# CAN.net
KiCad netlist of a schematic drawn in Altium Designer
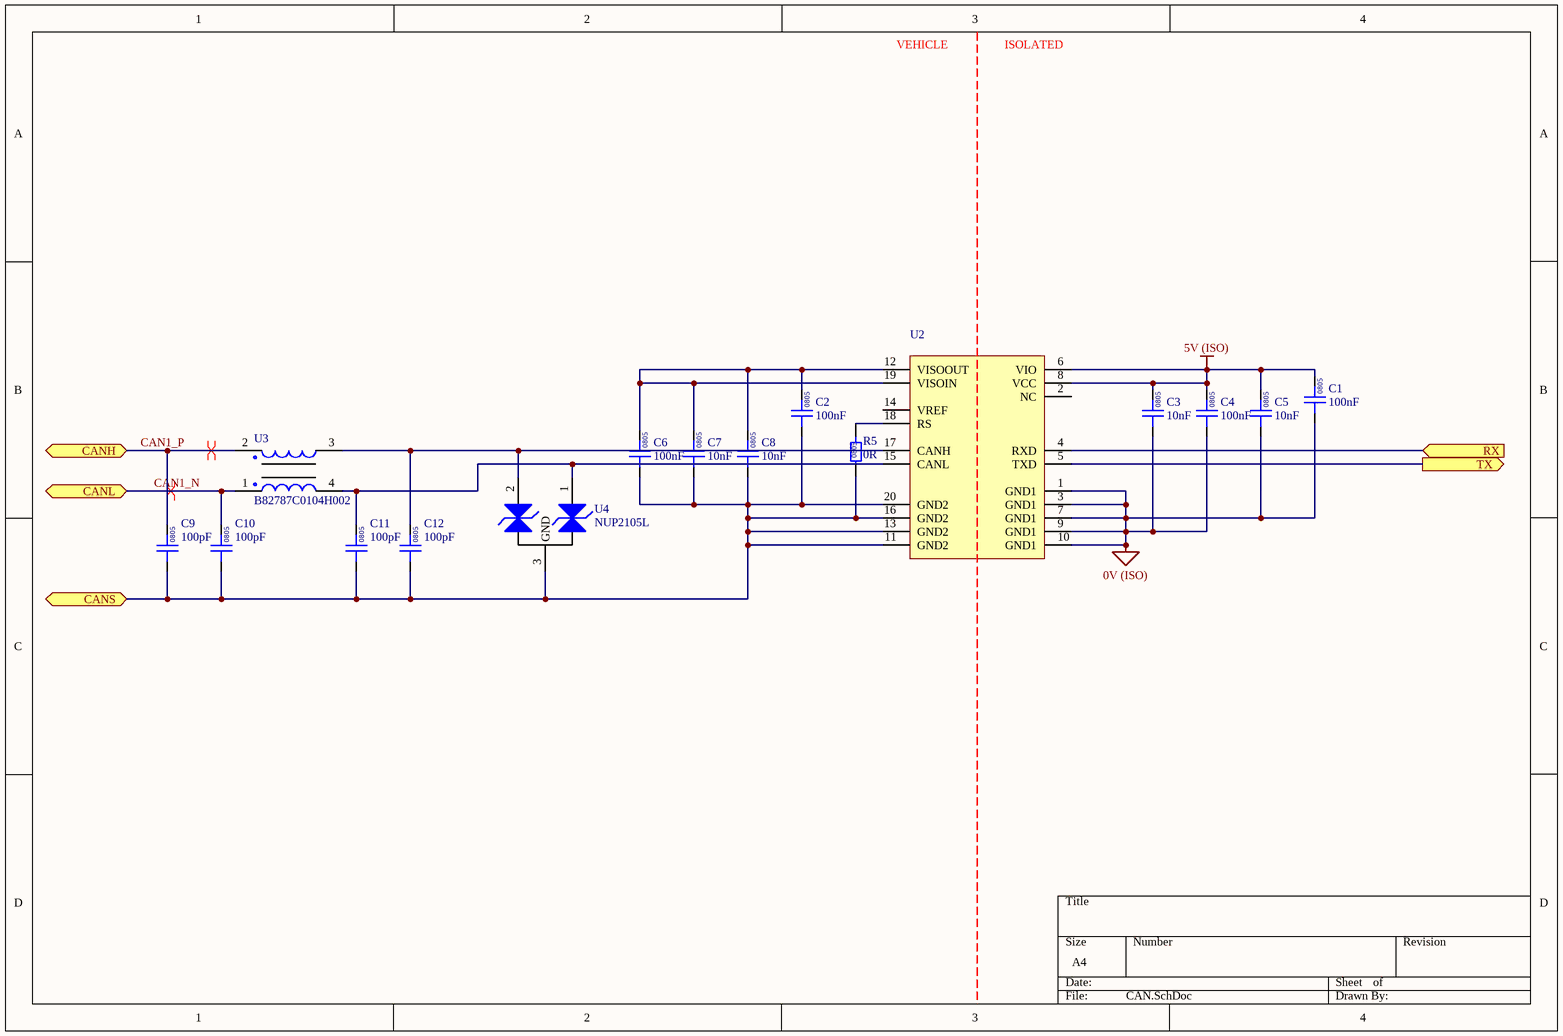
[diagram p0: CAN.SchDoc]

(export (version "E")
  (design (tool "Eeschema 10.0.6"))
  (components
    (comp (ref "C1")
      (value "100nF")
      (footprint "0805")
      (fields
        (field (name "PART NUMBER") "GCM21BR71H104KA37L")
        (field (name "TOLERANCE") "±10%")
        (field (name "MANUFACTURER") "muRata")
      )
      (libsource (lib "ts_standard_library") (part "Capacitor 0805"))
    )
    (comp (ref "C2")
      (value "100nF")
      (footprint "0805")
      (fields
        (field (name "PART NUMBER") "GCM21BR71H104KA37L")
        (field (name "TOLERANCE") "±10%")
        (field (name "MANUFACTURER") "muRata")
      )
      (libsource (lib "ts_standard_library") (part "Capacitor 0805"))
    )
    (comp (ref "C3")
      (value "10nF")
      (footprint "0805")
      (fields
        (field (name "PART NUMBER") "GCM2195C1H103JA16D")
        (field (name "TOLERANCE") "±5%")
        (field (name "MANUFACTURER") "muRata")
      )
      (libsource (lib "ts_standard_library") (part "Capacitor 0805"))
    )
    (comp (ref "C4")
      (value "100nF")
      (footprint "0805")
      (fields
        (field (name "PART NUMBER") "GCM21BR71H104KA37L")
        (field (name "TOLERANCE") "±10%")
        (field (name "MANUFACTURER") "muRata")
      )
      (libsource (lib "ts_standard_library") (part "Capacitor 0805"))
    )
    (comp (ref "C5")
      (value "10nF")
      (footprint "0805")
      (fields
        (field (name "PART NUMBER") "GCM2195C1H103JA16D")
        (field (name "TOLERANCE") "±5%")
        (field (name "MANUFACTURER") "muRata")
      )
      (libsource (lib "ts_standard_library") (part "Capacitor 0805"))
    )
    (comp (ref "C6")
      (value "100nF")
      (footprint "0805")
      (fields
        (field (name "PART NUMBER") "GCM21BR71H104KA37L")
        (field (name "TOLERANCE") "±10%")
        (field (name "MANUFACTURER") "muRata")
      )
      (libsource (lib "ts_standard_library") (part "Capacitor 0805"))
    )
    (comp (ref "C7")
      (value "10nF")
      (footprint "0805")
      (fields
        (field (name "PART NUMBER") "GCM2195C1H103JA16D")
        (field (name "TOLERANCE") "±5%")
        (field (name "MANUFACTURER") "muRata")
      )
      (libsource (lib "ts_standard_library") (part "Capacitor 0805"))
    )
    (comp (ref "C8")
      (value "10nF")
      (footprint "0805")
      (fields
        (field (name "PART NUMBER") "GCM2195C1H103JA16D")
        (field (name "TOLERANCE") "±5%")
        (field (name "MANUFACTURER") "muRata")
      )
      (libsource (lib "ts_standard_library") (part "Capacitor 0805"))
    )
    (comp (ref "C9")
      (value "100pF")
      (footprint "0805")
      (fields
        (field (name "PART NUMBER") "GCM2165C1H101JA16D")
        (field (name "TOLERANCE") "±5%")
        (field (name "MANUFACTURER") "muRata")
      )
      (libsource (lib "ts_standard_library") (part "Capacitor 0805"))
    )
    (comp (ref "C10")
      (value "100pF")
      (footprint "0805")
      (fields
        (field (name "PART NUMBER") "GCM2165C1H101JA16D")
        (field (name "TOLERANCE") "±5%")
        (field (name "MANUFACTURER") "muRata")
      )
      (libsource (lib "ts_standard_library") (part "Capacitor 0805"))
    )
    (comp (ref "C11")
      (value "100pF")
      (footprint "0805")
      (fields
        (field (name "PART NUMBER") "GCM2165C1H101JA16D")
        (field (name "TOLERANCE") "±5%")
        (field (name "MANUFACTURER") "muRata")
      )
      (libsource (lib "ts_standard_library") (part "Capacitor 0805"))
    )
    (comp (ref "C12")
      (value "100pF")
      (footprint "0805")
      (fields
        (field (name "PART NUMBER") "GCM2165C1H101JA16D")
        (field (name "TOLERANCE") "±5%")
        (field (name "MANUFACTURER") "muRata")
      )
      (libsource (lib "ts_standard_library") (part "Capacitor 0805"))
    )
    (comp (ref "R5")
      (value "0R")
      (footprint "0805")
      (fields
        (field (name "PART NUMBER") "RC0805FR070RL")
        (field (name "MANUFACTURER") "YAGEO")
        (field (name "TOLERANCE") "0.01")
      )
      (libsource (lib "ts_standard_library") (part "Resistor 0805"))
    )
    (comp (ref "U2")
      (value "~")
      (footprint "AD SOIC-W 20")
      (description "Isolated CAN Transceiver")
      (fields (field (name "PART NUMBER") "ADM3053") (field (name "MANUFACTURER") "Analogue Devices"))
      (libsource (lib "ts_standard_library") (part "ADM3053"))
    )
    (comp (ref "U3")
      (value "B82787C0104H002")
      (footprint "TDK 4-PC Pad")
      (fields
        (field (name "MANUFACTURER") "EPCOS (TDK)")
        (field (name "DIGIKEY PART NUMBER") "495-4598-1-ND")
      )
      (libsource (lib "ts_standard_library") (part "B82787C0104H002"))
    )
    (comp (ref "U4")
      (value "NUP2105L")
      (footprint "ON SOT-23")
      (description "Dual Line CAN Bus Protector")
      (fields
        (field (name "MANUFACTURER") "ON Semiconductor")
        (field (name "DIGIKEY PART NUMBER") "NUP2105LT1GOSCT-ND")
      )
      (libsource (lib "ts_standard_library") (part "NUP2105L"))
    )
  )
  (nets
    (net (code "1") (name "/CAN1_N") (class "Default")
      (node (ref "C10") (pin "2") (pinfunction "2_2") (pintype "passive"))
      (node (ref "U3") (pin "1") (pinfunction "1_1") (pintype "passive"))
    )
    (net (code "2") (name "/CAN1_P") (class "Default")
      (node (ref "C9") (pin "2") (pinfunction "2_2") (pintype "passive"))
      (node (ref "U3") (pin "2") (pinfunction "2_2") (pintype "passive"))
    )
    (net (code "3") (name "/CANS") (class "Default")
      (node (ref "C10") (pin "1") (pinfunction "1_1") (pintype "passive"))
      (node (ref "C11") (pin "1") (pinfunction "1_1") (pintype "passive"))
      (node (ref "C12") (pin "1") (pinfunction "1_1") (pintype "passive"))
      (node (ref "C2") (pin "1") (pinfunction "1_1") (pintype "passive"))
      (node (ref "C6") (pin "1") (pinfunction "1_1") (pintype "passive"))
      (node (ref "C7") (pin "1") (pinfunction "1_1") (pintype "passive"))
      (node (ref "C8") (pin "1") (pinfunction "1_1") (pintype "passive"))
      (node (ref "C9") (pin "1") (pinfunction "1_1") (pintype "passive"))
      (node (ref "R5") (pin "1") (pinfunction "1_1") (pintype "passive"))
      (node (ref "U2") (pin "11") (pinfunction "GND2_11") (pintype "passive"))
      (node (ref "U2") (pin "13") (pinfunction "GND2_13") (pintype "passive"))
      (node (ref "U2") (pin "16") (pinfunction "GND2_16") (pintype "passive"))
      (node (ref "U2") (pin "20") (pinfunction "GND2_20") (pintype "passive"))
      (node (ref "U4") (pin "3") (pinfunction "GND_3") (pintype "passive"))
    )
    (net (code "4") (name "/RX") (class "Default")
      (node (ref "U2") (pin "4") (pinfunction "RXD_4") (pintype "passive"))
    )
    (net (code "5") (name "/TX") (class "Default")
      (node (ref "U2") (pin "5") (pinfunction "TXD_5") (pintype "passive"))
    )
    (net (code "6") (name "0V (ISO)") (class "Default")
      (node (ref "C1") (pin "1") (pinfunction "1_1") (pintype "passive"))
      (node (ref "C3") (pin "1") (pinfunction "1_1") (pintype "passive"))
      (node (ref "C4") (pin "1") (pinfunction "1_1") (pintype "passive"))
      (node (ref "C5") (pin "1") (pinfunction "1_1") (pintype "passive"))
      (node (ref "U2") (pin "1") (pinfunction "GND1_1") (pintype "passive"))
      (node (ref "U2") (pin "10") (pinfunction "GND1_10") (pintype "passive"))
      (node (ref "U2") (pin "3") (pinfunction "GND1_3") (pintype "passive"))
      (node (ref "U2") (pin "7") (pinfunction "GND1_7") (pintype "passive"))
      (node (ref "U2") (pin "9") (pinfunction "GND1_9") (pintype "passive"))
    )
    (net (code "7") (name "5V (ISO)") (class "Default")
      (node (ref "C1") (pin "2") (pinfunction "2_2") (pintype "passive"))
      (node (ref "C3") (pin "2") (pinfunction "2_2") (pintype "passive"))
      (node (ref "C4") (pin "2") (pinfunction "2_2") (pintype "passive"))
      (node (ref "C5") (pin "2") (pinfunction "2_2") (pintype "passive"))
      (node (ref "U2") (pin "6") (pinfunction "VIO_6") (pintype "passive"))
      (node (ref "U2") (pin "8") (pinfunction "VCC_8") (pintype "passive"))
    )
    (net (code "8") (name "Net-(U2-CANH)") (class "Default")
      (node (ref "C12") (pin "2") (pinfunction "2_2") (pintype "passive"))
      (node (ref "U2") (pin "17") (pinfunction "CANH_17") (pintype "passive"))
      (node (ref "U3") (pin "3") (pinfunction "3_3") (pintype "passive"))
      (node (ref "U4") (pin "2") (pinfunction "CAN_L_2") (pintype "passive"))
    )
    (net (code "9") (name "Net-(U2-CANL)") (class "Default")
      (node (ref "C11") (pin "2") (pinfunction "2_2") (pintype "passive"))
      (node (ref "U2") (pin "15") (pinfunction "CANL_15") (pintype "passive"))
      (node (ref "U3") (pin "4") (pinfunction "4_4") (pintype "passive"))
      (node (ref "U4") (pin "1") (pinfunction "CAN_H_1") (pintype "passive"))
    )
    (net (code "10") (name "Net-(U2-RS)") (class "Default")
      (node (ref "R5") (pin "2") (pinfunction "2_2") (pintype "passive"))
      (node (ref "U2") (pin "18") (pinfunction "RS_18") (pintype "passive"))
    )
    (net (code "11") (name "Net-(U2-VISOIN)") (class "Default")
      (node (ref "C2") (pin "2") (pinfunction "2_2") (pintype "passive"))
      (node (ref "C6") (pin "2") (pinfunction "2_2") (pintype "passive"))
      (node (ref "C7") (pin "2") (pinfunction "2_2") (pintype "passive"))
      (node (ref "C8") (pin "2") (pinfunction "2_2") (pintype "passive"))
      (node (ref "U2") (pin "12") (pinfunction "VISOOUT_12") (pintype "passive"))
      (node (ref "U2") (pin "19") (pinfunction "VISOIN_19") (pintype "passive"))
    )
    (net (code "12") (name "unconnected-(U2-NC-Pad2)") (class "Default")
      (node (ref "U2") (pin "2") (pinfunction "NC_2") (pintype "passive"))
    )
    (net (code "13") (name "unconnected-(U2-VREF-Pad14)") (class "Default")
      (node (ref "U2") (pin "14") (pinfunction "VREF_14") (pintype "passive"))
    )
  )
)
